# Updiy.net
KiCad netlist of a schematic drawn in Altium Designer
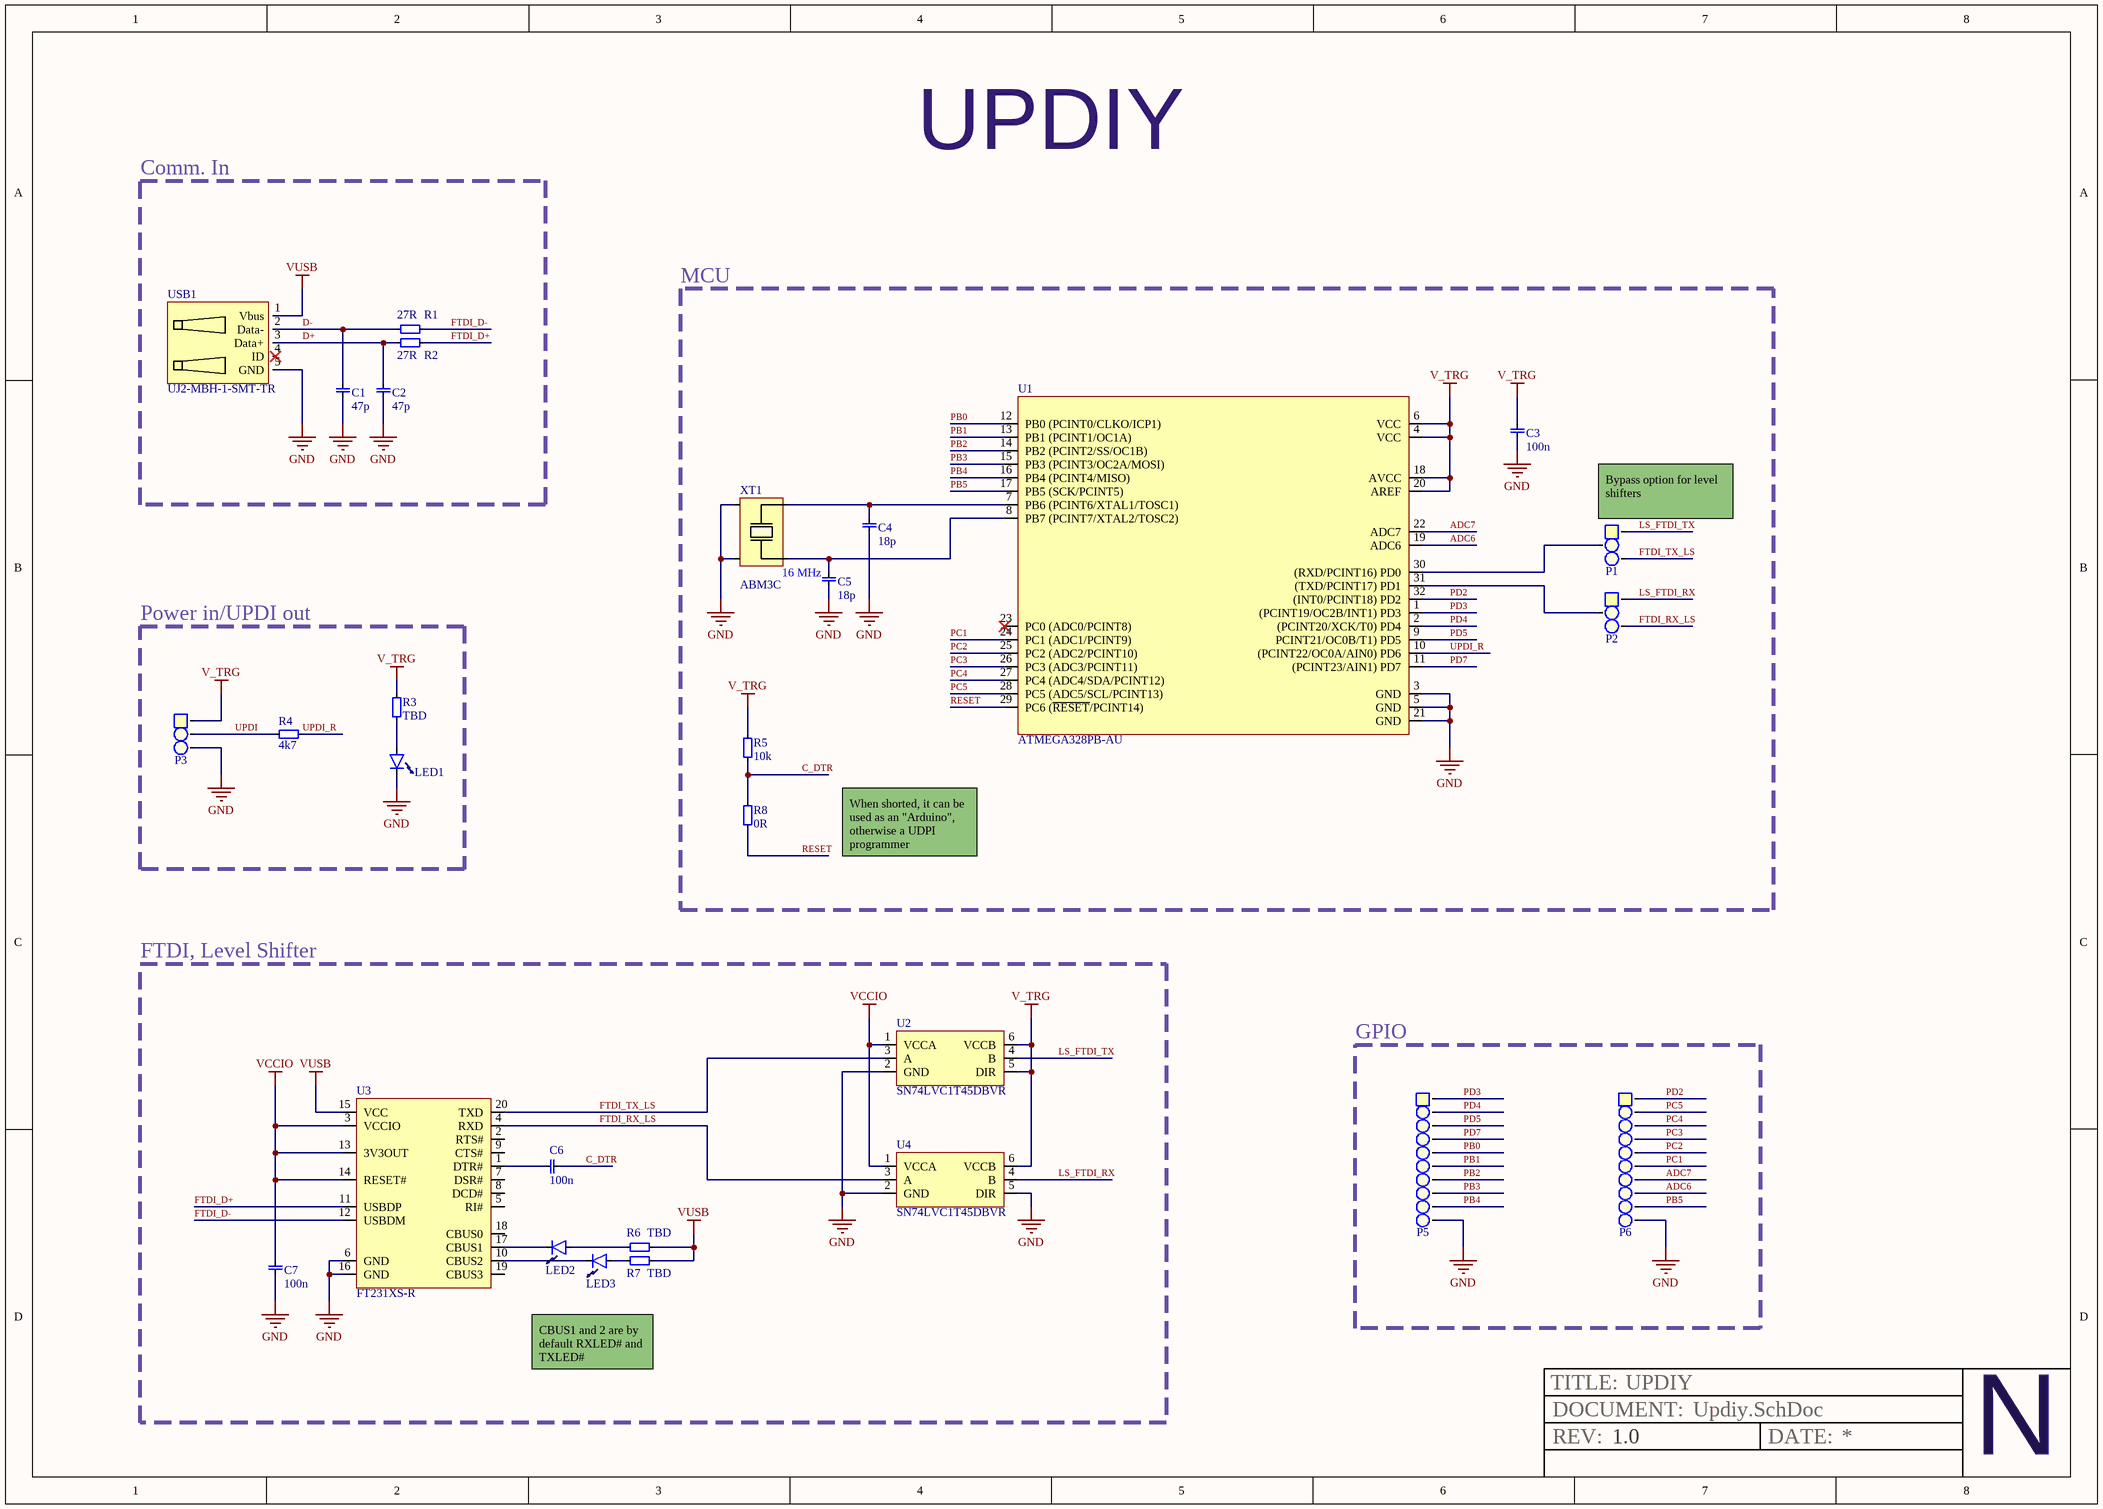
[diagram p0: Updiy.SchDoc]

(export (version "E")
  (design (tool "Eeschema 10.0.6"))
  (components
    (comp (ref "C1")
      (value "47p")
      (footprint "0805, cap")
      (fields (field (name "Comment") "0805, capacitor"))
      (libsource (lib "jclib") (part "0805, capacitor"))
    )
    (comp (ref "C2")
      (value "47p")
      (footprint "0805, cap")
      (fields (field (name "Comment") "0805, capacitor"))
      (libsource (lib "jclib") (part "0805, capacitor"))
    )
    (comp (ref "C3")
      (value "100n")
      (footprint "0805, cap")
      (fields (field (name "Comment") "0805, capacitor"))
      (libsource (lib "jclib") (part "0805, capacitor"))
    )
    (comp (ref "C4")
      (value "18p")
      (footprint "0805, cap")
      (fields (field (name "Comment") "0805, capacitor"))
      (libsource (lib "jclib") (part "0805, capacitor"))
    )
    (comp (ref "C5")
      (value "18p")
      (footprint "0805, cap")
      (fields (field (name "Comment") "0805, capacitor"))
      (libsource (lib "jclib") (part "0805, capacitor"))
    )
    (comp (ref "C6")
      (value "100n")
      (footprint "0805, cap")
      (fields (field (name "Comment") "0805, capacitor"))
      (libsource (lib "jclib") (part "0805, capacitor"))
    )
    (comp (ref "C7")
      (value "100n")
      (footprint "0805, cap")
      (fields (field (name "Comment") "0805, capacitor"))
      (libsource (lib "jclib") (part "0805, capacitor"))
    )
    (comp (ref "LED1")
      (value "0805, LED")
      (footprint "0805_led")
      (libsource (lib "jclib") (part "0805, LED"))
    )
    (comp (ref "LED2")
      (value "0805, LED")
      (footprint "0805_led")
      (libsource (lib "jclib") (part "0805, LED"))
    )
    (comp (ref "LED3")
      (value "0805, LED")
      (footprint "0805_led")
      (libsource (lib "jclib") (part "0805, LED"))
    )
    (comp (ref "P1")
      (value "1x3 Pin Header Mux")
      (footprint "padThree_L")
      (description "2.54 mm")
      (libsource (lib "jclib") (part "1x3 Pin Header Mux"))
    )
    (comp (ref "P2")
      (value "1x3 Pin Header Mux")
      (footprint "padThree_L")
      (description "2.54 mm")
      (libsource (lib "jclib") (part "1x3 Pin Header Mux"))
    )
    (comp (ref "P3")
      (value "1x3 Pin Header")
      (footprint "padThree_L")
      (description "2.54 mm")
      (libsource (lib "jclib") (part "1x3 Pin Header"))
    )
    (comp (ref "P5")
      (value "1x10 Pin Header")
      (footprint "1x10 PIN HEADER")
      (description "2.54 mm")
      (libsource (lib "jclib") (part "1x10 Pin Header"))
    )
    (comp (ref "P6")
      (value "1x10 Pin Header")
      (footprint "1x10 PIN HEADER")
      (description "2.54 mm")
      (libsource (lib "jclib") (part "1x10 Pin Header"))
    )
    (comp (ref "R1")
      (value "27R")
      (footprint "0805")
      (fields (field (name "Comment") "General resistor"))
      (libsource (lib "jclib") (part "resistor"))
    )
    (comp (ref "R2")
      (value "27R")
      (footprint "0805")
      (fields (field (name "Comment") "General resistor"))
      (libsource (lib "jclib") (part "resistor"))
    )
    (comp (ref "R3")
      (value "TBD")
      (footprint "0805")
      (fields (field (name "Comment") "General resistor"))
      (libsource (lib "jclib") (part "resistor"))
    )
    (comp (ref "R4")
      (value "4k7")
      (footprint "0805")
      (fields (field (name "Comment") "General resistor"))
      (libsource (lib "jclib") (part "resistor"))
    )
    (comp (ref "R5")
      (value "10k")
      (footprint "0805")
      (fields (field (name "Comment") "General resistor"))
      (libsource (lib "jclib") (part "resistor"))
    )
    (comp (ref "R6")
      (value "TBD")
      (footprint "0805")
      (fields (field (name "Comment") "General resistor"))
      (libsource (lib "jclib") (part "resistor"))
    )
    (comp (ref "R7")
      (value "TBD")
      (footprint "0805")
      (fields (field (name "Comment") "General resistor"))
      (libsource (lib "jclib") (part "resistor"))
    )
    (comp (ref "R8")
      (value "0R")
      (footprint "0805")
      (fields (field (name "Comment") "General resistor"))
      (libsource (lib "jclib") (part "resistor"))
    )
    (comp (ref "U1")
      (value "ATMEGA328PB-AU")
      (footprint "TQFP32_P08MM")
      (description "RISC Microcontroller, CMOS")
      (fields (field (name "MANUFACTURER") "Microchip"))
      (libsource (lib "jclib") (part "ATMEGA328PB-AU"))
    )
    (comp (ref "U2")
      (value "SN74LVC1T45DBVR")
      (footprint "SOT23-6")
      (description "Bus Transceiver, LVC/LCX/Z Series, 1-Func, 1-Bit, True Output, CMOS, PDSO6, Level shift")
      (fields (field (name "MANUFACTURER") "Texas Instruments"))
      (libsource (lib "jclib") (part "SN74LVC1T45DBVR"))
    )
    (comp (ref "U3")
      (value "FT231XS-R")
      (footprint "SSOP-20_P0.635")
      (description "Microprocessor Circuit, CMOS, PDSO20")
      (fields (field (name "MANUFACTURER") "FTDI"))
      (libsource (lib "jclib") (part "FT231XS-R"))
    )
    (comp (ref "U4")
      (value "SN74LVC1T45DBVR")
      (footprint "SOT23-6")
      (description "Bus Transceiver, LVC/LCX/Z Series, 1-Func, 1-Bit, True Output, CMOS, PDSO6, Level shift")
      (fields (field (name "MANUFACTURER") "Texas Instruments"))
      (libsource (lib "jclib") (part "SN74LVC1T45DBVR"))
    )
    (comp (ref "USB1")
      (value "UJ2-MBH-1-SMT-TR")
      (footprint "USB-MINI_UJ2-MBH-SMT")
      (description "USB Connector, 5 Contact(s), Female, Right Angle, Surface Mount Terminal, Receptacle")
      (fields (field (name "MANUFACTURER") "CUI Devices"))
      (libsource (lib "jclib") (part "USB Mini SMD"))
    )
    (comp (ref "XT1")
      (value "ABM3C")
      (footprint "ABM3B")
      (description "16 MHz")
      (libsource (lib "jclib") (part "XTAL ABM3C"))
    )
  )
  (nets
    (net (code "1") (name "/ADC6") (class "Default")
      (node (ref "P6") (pin "8") (pinfunction "8_8") (pintype "passive"))
      (node (ref "U1") (pin "19") (pinfunction "ADC6_19") (pintype "passive"))
    )
    (net (code "2") (name "/ADC7") (class "Default")
      (node (ref "P6") (pin "7") (pinfunction "7_7") (pintype "passive"))
      (node (ref "U1") (pin "22") (pinfunction "ADC7_22") (pintype "passive"))
    )
    (net (code "3") (name "/C_DTR") (class "Default")
      (node (ref "C6") (pin "0") (pinfunction "0_0") (pintype "passive"))
      (node (ref "R5") (pin "0") (pinfunction "0_0") (pintype "passive"))
      (node (ref "R8") (pin "1") (pinfunction "1_1") (pintype "passive"))
    )
    (net (code "4") (name "/D+") (class "Default")
      (node (ref "C2") (pin "1") (pinfunction "1_1") (pintype "passive"))
      (node (ref "R2") (pin "1") (pinfunction "1_1") (pintype "passive"))
      (node (ref "USB1") (pin "3") (pinfunction "Data+_3") (pintype "passive"))
    )
    (net (code "5") (name "/D-") (class "Default")
      (node (ref "C1") (pin "1") (pinfunction "1_1") (pintype "passive"))
      (node (ref "R1") (pin "1") (pinfunction "1_1") (pintype "passive"))
      (node (ref "USB1") (pin "2") (pinfunction "Data-_2") (pintype "passive"))
    )
    (net (code "6") (name "/FTDI_D+") (class "Default")
      (node (ref "R2") (pin "0") (pinfunction "0_0") (pintype "passive"))
      (node (ref "U3") (pin "11") (pinfunction "USBDP_11") (pintype "passive"))
    )
    (net (code "7") (name "/FTDI_D-") (class "Default")
      (node (ref "R1") (pin "0") (pinfunction "0_0") (pintype "passive"))
      (node (ref "U3") (pin "12") (pinfunction "USBDM_12") (pintype "passive"))
    )
    (net (code "8") (name "/FTDI_RX_LS") (class "Default")
      (node (ref "P2") (pin "3") (pinfunction "3_3") (pintype "passive"))
      (node (ref "U3") (pin "4") (pinfunction "RXD_4") (pintype "passive"))
      (node (ref "U4") (pin "3") (pinfunction "A_3") (pintype "passive"))
    )
    (net (code "9") (name "/FTDI_TX_LS") (class "Default")
      (node (ref "P1") (pin "3") (pinfunction "3_3") (pintype "passive"))
      (node (ref "U2") (pin "3") (pinfunction "A_3") (pintype "passive"))
      (node (ref "U3") (pin "20") (pinfunction "TXD_20") (pintype "passive"))
    )
    (net (code "10") (name "/LS_FTDI_RX") (class "Default")
      (node (ref "P2") (pin "1") (pinfunction "1_1") (pintype "passive"))
      (node (ref "U4") (pin "4") (pinfunction "B_4") (pintype "passive"))
    )
    (net (code "11") (name "/LS_FTDI_TX") (class "Default")
      (node (ref "P1") (pin "1") (pinfunction "1_1") (pintype "passive"))
      (node (ref "U2") (pin "4") (pinfunction "B_4") (pintype "passive"))
    )
    (net (code "12") (name "/PB0") (class "Default")
      (node (ref "P5") (pin "5") (pinfunction "5_5") (pintype "passive"))
      (node (ref "U1") (pin "12") (pinfunction "PB0_(PCINT0/CLKO/ICP1)_12") (pintype "passive"))
    )
    (net (code "13") (name "/PB1") (class "Default")
      (node (ref "P5") (pin "6") (pinfunction "6_6") (pintype "passive"))
      (node (ref "U1") (pin "13") (pinfunction "PB1_(PCINT1/OC1A)_13") (pintype "passive"))
    )
    (net (code "14") (name "/PB2") (class "Default")
      (node (ref "P5") (pin "7") (pinfunction "7_7") (pintype "passive"))
      (node (ref "U1") (pin "14") (pinfunction "PB2_(PCINT2/SS/OC1B)_14") (pintype "passive"))
    )
    (net (code "15") (name "/PB3") (class "Default")
      (node (ref "P5") (pin "8") (pinfunction "8_8") (pintype "passive"))
      (node (ref "U1") (pin "15") (pinfunction "PB3_(PCINT3/OC2A/MOSI)_15") (pintype "passive"))
    )
    (net (code "16") (name "/PB4") (class "Default")
      (node (ref "P5") (pin "9") (pinfunction "9_9") (pintype "passive"))
      (node (ref "U1") (pin "16") (pinfunction "PB4_(PCINT4/MISO)_16") (pintype "passive"))
    )
    (net (code "17") (name "/PB5") (class "Default")
      (node (ref "P6") (pin "9") (pinfunction "9_9") (pintype "passive"))
      (node (ref "U1") (pin "17") (pinfunction "PB5_(SCK/PCINT5)_17") (pintype "passive"))
    )
    (net (code "18") (name "/PC1") (class "Default")
      (node (ref "P6") (pin "6") (pinfunction "6_6") (pintype "passive"))
      (node (ref "U1") (pin "24") (pinfunction "PC1_(ADC1/PCINT9)_24") (pintype "passive"))
    )
    (net (code "19") (name "/PC2") (class "Default")
      (node (ref "P6") (pin "5") (pinfunction "5_5") (pintype "passive"))
      (node (ref "U1") (pin "25") (pinfunction "PC2_(ADC2/PCINT10)_25") (pintype "passive"))
    )
    (net (code "20") (name "/PC3") (class "Default")
      (node (ref "P6") (pin "4") (pinfunction "4_4") (pintype "passive"))
      (node (ref "U1") (pin "26") (pinfunction "PC3_(ADC3/PCINT11)_26") (pintype "passive"))
    )
    (net (code "21") (name "/PC4") (class "Default")
      (node (ref "P6") (pin "3") (pinfunction "3_3") (pintype "passive"))
      (node (ref "U1") (pin "27") (pinfunction "PC4_(ADC4/SDA/PCINT12)_27") (pintype "passive"))
    )
    (net (code "22") (name "/PC5") (class "Default")
      (node (ref "P6") (pin "2") (pinfunction "2_2") (pintype "passive"))
      (node (ref "U1") (pin "28") (pinfunction "PC5_(ADC5/SCL/PCINT13)_28") (pintype "passive"))
    )
    (net (code "23") (name "/PD2") (class "Default")
      (node (ref "P6") (pin "1") (pinfunction "1_1") (pintype "passive"))
      (node (ref "U1") (pin "32") (pinfunction "(INT0/PCINT18)_PD2_32") (pintype "passive"))
    )
    (net (code "24") (name "/PD3") (class "Default")
      (node (ref "P5") (pin "1") (pinfunction "1_1") (pintype "passive"))
      (node (ref "U1") (pin "1") (pinfunction "(PCINT19/OC2B/INT1)_PD3_1") (pintype "passive"))
    )
    (net (code "25") (name "/PD4") (class "Default")
      (node (ref "P5") (pin "2") (pinfunction "2_2") (pintype "passive"))
      (node (ref "U1") (pin "2") (pinfunction "(PCINT20/XCK/T0)_PD4_2") (pintype "passive"))
    )
    (net (code "26") (name "/PD5") (class "Default")
      (node (ref "P5") (pin "3") (pinfunction "3_3") (pintype "passive"))
      (node (ref "U1") (pin "9") (pinfunction "PCINT21/OC0B/T1)_PD5_9") (pintype "passive"))
    )
    (net (code "27") (name "/PD7") (class "Default")
      (node (ref "P5") (pin "4") (pinfunction "4_4") (pintype "passive"))
      (node (ref "U1") (pin "11") (pinfunction "(PCINT23/AIN1)_PD7_11") (pintype "passive"))
    )
    (net (code "28") (name "/RESET") (class "Default")
      (node (ref "R8") (pin "0") (pinfunction "0_0") (pintype "passive"))
      (node (ref "U1") (pin "29") (pinfunction "PC6_(~{RESET}/PCINT14)_29") (pintype "passive"))
    )
    (net (code "29") (name "/UPDI") (class "Default")
      (node (ref "P3") (pin "2") (pinfunction "2_2") (pintype "passive"))
      (node (ref "R4") (pin "1") (pinfunction "1_1") (pintype "passive"))
    )
    (net (code "30") (name "/UPDI_R") (class "Default")
      (node (ref "R4") (pin "0") (pinfunction "0_0") (pintype "passive"))
      (node (ref "U1") (pin "10") (pinfunction "(PCINT22/OC0A/AIN0)_PD6_10") (pintype "passive"))
    )
    (net (code "31") (name "GND") (class "Default")
      (node (ref "C1") (pin "0") (pinfunction "0_0") (pintype "passive"))
      (node (ref "C2") (pin "0") (pinfunction "0_0") (pintype "passive"))
      (node (ref "C3") (pin "1") (pinfunction "1_1") (pintype "passive"))
      (node (ref "C4") (pin "0") (pinfunction "0_0") (pintype "passive"))
      (node (ref "C5") (pin "0") (pinfunction "0_0") (pintype "passive"))
      (node (ref "C7") (pin "0") (pinfunction "0_0") (pintype "passive"))
      (node (ref "LED1") (pin "0") (pinfunction "Cathode_0") (pintype "passive"))
      (node (ref "P3") (pin "3") (pinfunction "3_3") (pintype "passive"))
      (node (ref "P5") (pin "10") (pinfunction "10_10") (pintype "passive"))
      (node (ref "P6") (pin "10") (pinfunction "10_10") (pintype "passive"))
      (node (ref "U1") (pin "21") (pinfunction "GND_21") (pintype "passive"))
      (node (ref "U1") (pin "3") (pinfunction "GND_3") (pintype "passive"))
      (node (ref "U1") (pin "5") (pinfunction "GND_5") (pintype "passive"))
      (node (ref "U2") (pin "2") (pinfunction "GND_2") (pintype "passive"))
      (node (ref "U3") (pin "16") (pinfunction "GND_16") (pintype "passive"))
      (node (ref "U3") (pin "6") (pinfunction "GND_6") (pintype "passive"))
      (node (ref "U4") (pin "2") (pinfunction "GND_2") (pintype "passive"))
      (node (ref "U4") (pin "5") (pinfunction "DIR_5") (pintype "passive"))
      (node (ref "USB1") (pin "5") (pinfunction "GND_5") (pintype "passive"))
      (node (ref "XT1") (pin "2") (pinfunction "2_2") (pintype "passive"))
      (node (ref "XT1") (pin "4") (pinfunction "4_4") (pintype "passive"))
    )
    (net (code "32") (name "Net-(LED1-Pad1)") (class "Default")
      (node (ref "LED1") (pin "1") (pinfunction "1_1") (pintype "passive"))
      (node (ref "R3") (pin "0") (pinfunction "0_0") (pintype "passive"))
    )
    (net (code "33") (name "Net-(LED2-Cathode)") (class "Default")
      (node (ref "LED2") (pin "0") (pinfunction "Cathode_0") (pintype "passive"))
      (node (ref "U3") (pin "17") (pinfunction "CBUS1_17") (pintype "passive"))
    )
    (net (code "34") (name "Net-(LED2-Pad1)") (class "Default")
      (node (ref "LED2") (pin "1") (pinfunction "1_1") (pintype "passive"))
      (node (ref "R6") (pin "0") (pinfunction "0_0") (pintype "passive"))
    )
    (net (code "35") (name "Net-(LED3-Cathode)") (class "Default")
      (node (ref "LED3") (pin "0") (pinfunction "Cathode_0") (pintype "passive"))
      (node (ref "U3") (pin "10") (pinfunction "CBUS2_10") (pintype "passive"))
    )
    (net (code "36") (name "Net-(LED3-Pad1)") (class "Default")
      (node (ref "LED3") (pin "1") (pinfunction "1_1") (pintype "passive"))
      (node (ref "R7") (pin "1") (pinfunction "1_1") (pintype "passive"))
    )
    (net (code "37") (name "Net-(U1-(RXD{slash}PCINT16)_PD0)") (class "Default")
      (node (ref "P1") (pin "2") (pinfunction "2_2") (pintype "passive"))
      (node (ref "U1") (pin "30") (pinfunction "(RXD/PCINT16)_PD0_30") (pintype "passive"))
    )
    (net (code "38") (name "Net-(U1-(TXD{slash}PCINT17)_PD1)") (class "Default")
      (node (ref "P2") (pin "2") (pinfunction "2_2") (pintype "passive"))
      (node (ref "U1") (pin "31") (pinfunction "(TXD/PCINT17)_PD1_31") (pintype "passive"))
    )
    (net (code "39") (name "Net-(U1-PB6_(PCINT6{slash}XTAL1{slash}TOSC1))") (class "Default")
      (node (ref "C4") (pin "1") (pinfunction "1_1") (pintype "passive"))
      (node (ref "U1") (pin "7") (pinfunction "PB6_(PCINT6/XTAL1/TOSC1)_7") (pintype "passive"))
      (node (ref "XT1") (pin "1") (pinfunction "1_1") (pintype "passive"))
    )
    (net (code "40") (name "Net-(U1-PB7_(PCINT7{slash}XTAL2{slash}TOSC2))") (class "Default")
      (node (ref "C5") (pin "1") (pinfunction "1_1") (pintype "passive"))
      (node (ref "U1") (pin "8") (pinfunction "PB7_(PCINT7/XTAL2/TOSC2)_8") (pintype "passive"))
      (node (ref "XT1") (pin "3") (pinfunction "3_3") (pintype "passive"))
    )
    (net (code "41") (name "Net-(U3-DTR#)") (class "Default")
      (node (ref "C6") (pin "1") (pinfunction "1_1") (pintype "passive"))
      (node (ref "U3") (pin "1") (pinfunction "DTR#_1") (pintype "passive"))
    )
    (net (code "42") (name "VCCIO") (class "Default")
      (node (ref "C7") (pin "1") (pinfunction "1_1") (pintype "passive"))
      (node (ref "U2") (pin "1") (pinfunction "VCCA_1") (pintype "passive"))
      (node (ref "U3") (pin "13") (pinfunction "3V3OUT_13") (pintype "passive"))
      (node (ref "U3") (pin "14") (pinfunction "RESET#_14") (pintype "passive"))
      (node (ref "U3") (pin "3") (pinfunction "VCCIO_3") (pintype "passive"))
      (node (ref "U4") (pin "1") (pinfunction "VCCA_1") (pintype "passive"))
    )
    (net (code "43") (name "VUSB") (class "Default")
      (node (ref "R6") (pin "1") (pinfunction "1_1") (pintype "passive"))
      (node (ref "R7") (pin "0") (pinfunction "0_0") (pintype "passive"))
      (node (ref "U3") (pin "15") (pinfunction "VCC_15") (pintype "passive"))
      (node (ref "USB1") (pin "1") (pinfunction "Vbus_1") (pintype "passive"))
    )
    (net (code "44") (name "V_TRG") (class "Default")
      (node (ref "C3") (pin "0") (pinfunction "0_0") (pintype "passive"))
      (node (ref "P3") (pin "1") (pinfunction "1_1") (pintype "passive"))
      (node (ref "R3") (pin "1") (pinfunction "1_1") (pintype "passive"))
      (node (ref "R5") (pin "1") (pinfunction "1_1") (pintype "passive"))
      (node (ref "U1") (pin "18") (pinfunction "AVCC_18") (pintype "passive"))
      (node (ref "U1") (pin "20") (pinfunction "AREF_20") (pintype "passive"))
      (node (ref "U1") (pin "4") (pinfunction "VCC_4") (pintype "passive"))
      (node (ref "U1") (pin "6") (pinfunction "VCC_6") (pintype "passive"))
      (node (ref "U2") (pin "5") (pinfunction "DIR_5") (pintype "passive"))
      (node (ref "U2") (pin "6") (pinfunction "VCCB_6") (pintype "passive"))
      (node (ref "U4") (pin "6") (pinfunction "VCCB_6") (pintype "passive"))
    )
    (net (code "45") (name "unconnected-(U1-PC0_(ADC0{slash}PCINT8)-Pad23)") (class "Default")
      (node (ref "U1") (pin "23") (pinfunction "PC0_(ADC0/PCINT8)_23") (pintype "passive+no_connect"))
    )
    (net (code "46") (name "unconnected-(U3-CBUS0-Pad18)") (class "Default")
      (node (ref "U3") (pin "18") (pinfunction "CBUS0_18") (pintype "passive"))
    )
    (net (code "47") (name "unconnected-(U3-CBUS3-Pad19)") (class "Default")
      (node (ref "U3") (pin "19") (pinfunction "CBUS3_19") (pintype "passive"))
    )
    (net (code "48") (name "unconnected-(U3-CTS#-Pad9)") (class "Default")
      (node (ref "U3") (pin "9") (pinfunction "CTS#_9") (pintype "passive"))
    )
    (net (code "49") (name "unconnected-(U3-DCD#-Pad8)") (class "Default")
      (node (ref "U3") (pin "8") (pinfunction "DCD#_8") (pintype "passive"))
    )
    (net (code "50") (name "unconnected-(U3-DSR#-Pad7)") (class "Default")
      (node (ref "U3") (pin "7") (pinfunction "DSR#_7") (pintype "passive"))
    )
    (net (code "51") (name "unconnected-(U3-RI#-Pad5)") (class "Default")
      (node (ref "U3") (pin "5") (pinfunction "RI#_5") (pintype "passive"))
    )
    (net (code "52") (name "unconnected-(U3-RTS#-Pad2)") (class "Default")
      (node (ref "U3") (pin "2") (pinfunction "RTS#_2") (pintype "passive"))
    )
    (net (code "53") (name "unconnected-(USB1-ID-Pad4)") (class "Default")
      (node (ref "USB1") (pin "4") (pinfunction "ID_4") (pintype "passive+no_connect"))
    )
  )
)
